# MOTORS.net
KiCad netlist of a schematic drawn in Altium Designer
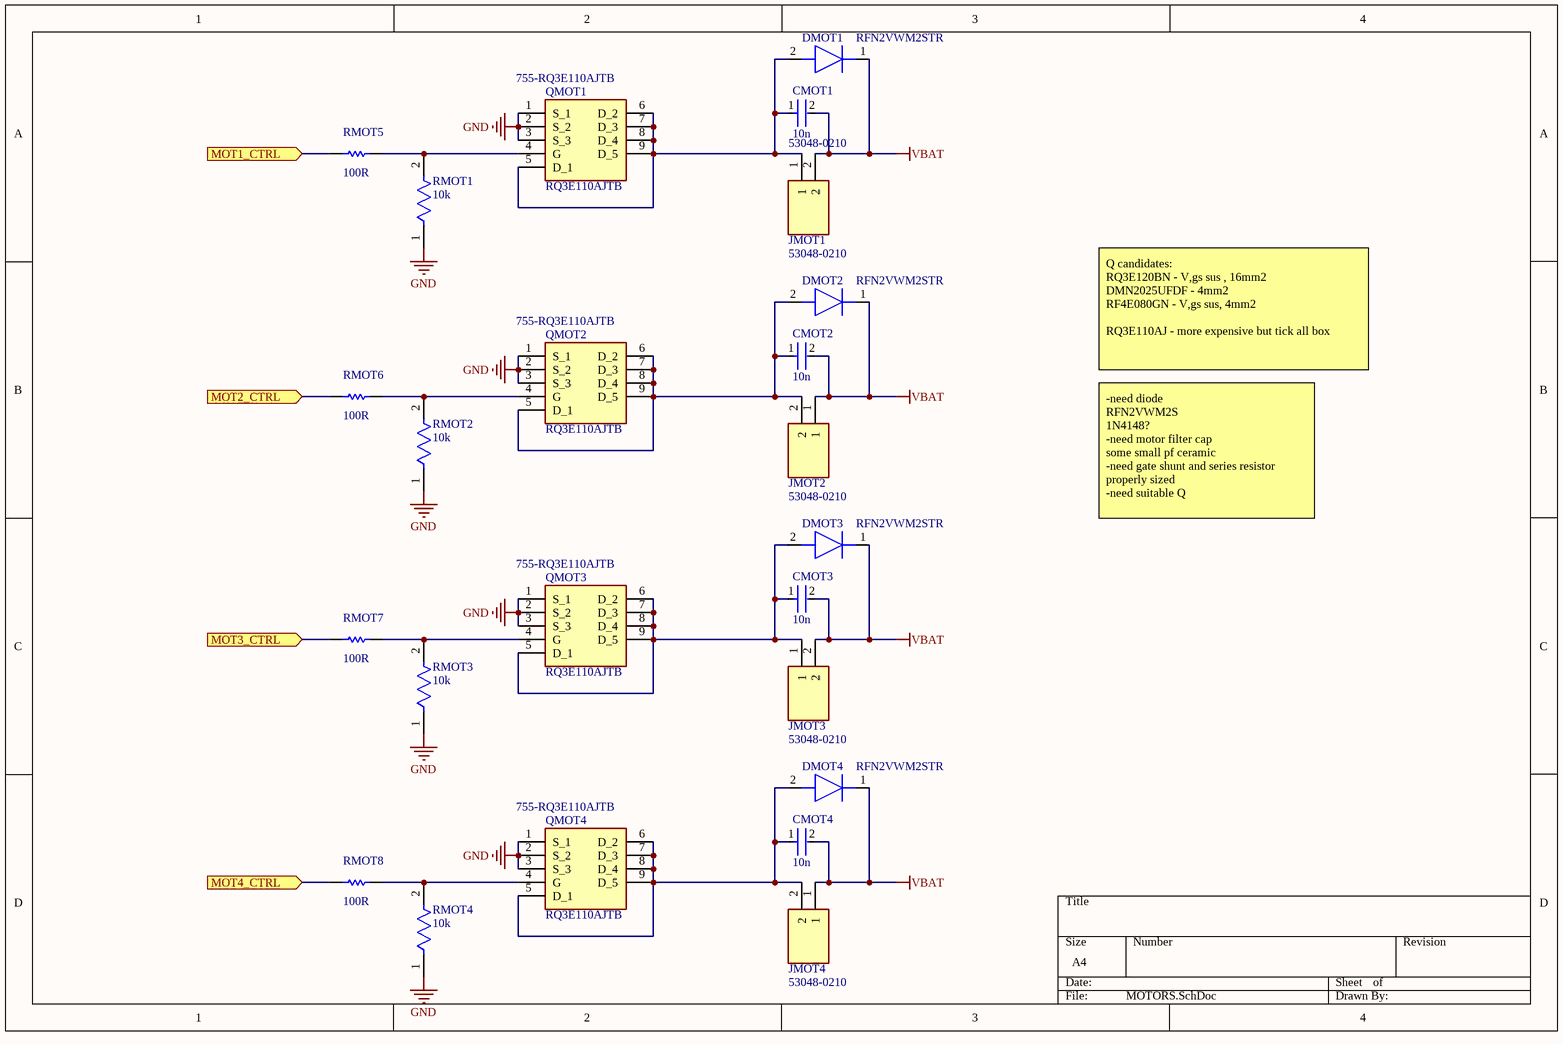
[diagram p0: MOTORS.SchDoc]

(export (version "E")
  (design (tool "Eeschema 10.0.6"))
  (components
    (comp (ref "CMOT1")
      (value "10n")
      (footprint "FP-CL10-IPC_A")
      (description "Cap Ceramic 10nF 50V X7R ±10% Pad SMD 0603 +125°C T/R")
      (fields (field (name "TOLERANCE") "10%") (field (name "VOLTAGE") "50V"))
      (libsource (lib "Altium Content Vault") (part "b4654b650e69147ec39a6b967a45e02"))
    )
    (comp (ref "CMOT2")
      (value "10n")
      (footprint "FP-CL10-IPC_A")
      (description "Cap Ceramic 10nF 50V X7R ±10% Pad SMD 0603 +125°C T/R")
      (fields (field (name "TOLERANCE") "10%") (field (name "VOLTAGE") "50V"))
      (libsource (lib "Altium Content Vault") (part "b4654b650e69147ec39a6b967a45e02"))
    )
    (comp (ref "CMOT3")
      (value "10n")
      (footprint "FP-CL10-IPC_A")
      (description "Cap Ceramic 10nF 50V X7R ±10% Pad SMD 0603 +125°C T/R")
      (fields (field (name "TOLERANCE") "10%") (field (name "VOLTAGE") "50V"))
      (libsource (lib "Altium Content Vault") (part "b4654b650e69147ec39a6b967a45e02"))
    )
    (comp (ref "CMOT4")
      (value "10n")
      (footprint "FP-CL10-IPC_A")
      (description "Cap Ceramic 10nF 50V X7R ±10% Pad SMD 0603 +125°C T/R")
      (fields (field (name "TOLERANCE") "10%") (field (name "VOLTAGE") "50V"))
      (libsource (lib "Altium Content Vault") (part "b4654b650e69147ec39a6b967a45e02"))
    )
    (comp (ref "DMOT1")
      (value "RFN2VWM2STR")
      (footprint "RFN2VWM2STR")
      (description "Diodes - General Purpose")
      (fields (field (name "MOUSER PART NUMBER") "755-RFN2VWM2STR"))
      (libsource (lib "James Whitehead") (part "RFN2VWM2STR"))
    )
    (comp (ref "DMOT2")
      (value "RFN2VWM2STR")
      (footprint "RFN2VWM2STR")
      (description "Diodes - General Purpose")
      (fields (field (name "MOUSER PART NUMBER") "755-RFN2VWM2STR"))
      (libsource (lib "James Whitehead") (part "RFN2VWM2STR"))
    )
    (comp (ref "DMOT3")
      (value "RFN2VWM2STR")
      (footprint "RFN2VWM2STR")
      (description "Diodes - General Purpose")
      (fields (field (name "MOUSER PART NUMBER") "755-RFN2VWM2STR"))
      (libsource (lib "James Whitehead") (part "RFN2VWM2STR"))
    )
    (comp (ref "DMOT4")
      (value "RFN2VWM2STR")
      (footprint "RFN2VWM2STR")
      (description "Diodes - General Purpose")
      (fields (field (name "MOUSER PART NUMBER") "755-RFN2VWM2STR"))
      (libsource (lib "James Whitehead") (part "RFN2VWM2STR"))
    )
    (comp (ref "JMOT1")
      (value "53048-0210")
      (footprint "SamacSys:SHDRRA2W35P0X125_1X2_425X550X350P")
      (description "Connector")
      (fields
        (field (name "MOUSER PART NUMBER") "538-53048-0210")
        (field (name "SUPPLIER PART NUMBER 1") "53048-0210")
      )
      (libsource (lib "*") (part "53048-0210"))
    )
    (comp (ref "JMOT2")
      (value "53048-0210")
      (footprint "SamacSys:SHDRRA2W35P0X125_1X2_425X550X350P")
      (description "Connector")
      (fields (field (name "MOUSER PART NUMBER") "538-53048-0210"))
      (libsource (lib "") (part "53048-0210_1"))
    )
    (comp (ref "JMOT3")
      (value "53048-0210")
      (footprint "SamacSys:SHDRRA2W35P0X125_1X2_425X550X350P")
      (description "Connector")
      (fields (field (name "MOUSER PART NUMBER") "538-53048-0210"))
      (libsource (lib "*") (part "53048-0210"))
    )
    (comp (ref "JMOT4")
      (value "53048-0210")
      (footprint "SamacSys:SHDRRA2W35P0X125_1X2_425X550X350P")
      (description "Connector")
      (fields (field (name "MOUSER PART NUMBER") "538-53048-0210"))
      (libsource (lib "") (part "53048-0210_1"))
    )
    (comp (ref "QMOT1")
      (value "RQ3E110AJTB")
      (footprint "SamacSys:RQ3E110AJTB")
      (description "MOSFET (N-Channel)")
      (fields
        (field (name "MOUSER PART NUMBER") "755-RQ3E110AJTB")
        (field (name "SUPPLIER PART NUMBER 1") "755-RQ3E110AJTB")
      )
      (libsource (lib "*") (part "RQ3E110AJTB"))
    )
    (comp (ref "QMOT2")
      (value "RQ3E110AJTB")
      (footprint "SamacSys:RQ3E110AJTB")
      (description "MOSFET (N-Channel)")
      (fields
        (field (name "MOUSER PART NUMBER") "755-RQ3E110AJTB")
        (field (name "SUPPLIER PART NUMBER 1") "755-RQ3E110AJTB")
      )
      (libsource (lib "*") (part "RQ3E110AJTB"))
    )
    (comp (ref "QMOT3")
      (value "RQ3E110AJTB")
      (footprint "SamacSys:RQ3E110AJTB")
      (description "MOSFET (N-Channel)")
      (fields
        (field (name "MOUSER PART NUMBER") "755-RQ3E110AJTB")
        (field (name "SUPPLIER PART NUMBER 1") "755-RQ3E110AJTB")
      )
      (libsource (lib "*") (part "RQ3E110AJTB"))
    )
    (comp (ref "QMOT4")
      (value "RQ3E110AJTB")
      (footprint "SamacSys:RQ3E110AJTB")
      (description "MOSFET (N-Channel)")
      (fields
        (field (name "MOUSER PART NUMBER") "755-RQ3E110AJTB")
        (field (name "SUPPLIER PART NUMBER 1") "755-RQ3E110AJTB")
      )
      (libsource (lib "*") (part "RQ3E110AJTB"))
    )
    (comp (ref "RMOT1")
      (value "10k")
      (footprint "FP-ERJ3G-IPC_C")
      (description "RES SMD 10K OHM 5% 1/10W 0603")
      (fields (field (name "TOLERANCE") "5%"))
      (libsource (lib "Altium Content Vault") (part "1029c3af85768c4190bb7ad29bc67b5"))
    )
    (comp (ref "RMOT2")
      (value "10k")
      (footprint "FP-ERJ3G-IPC_C")
      (description "RES SMD 10K OHM 5% 1/10W 0603")
      (fields (field (name "TOLERANCE") "5%"))
      (libsource (lib "Altium Content Vault") (part "1029c3af85768c4190bb7ad29bc67b5"))
    )
    (comp (ref "RMOT3")
      (value "10k")
      (footprint "FP-ERJ3G-IPC_C")
      (description "RES SMD 10K OHM 5% 1/10W 0603")
      (fields (field (name "TOLERANCE") "5%"))
      (libsource (lib "Altium Content Vault") (part "1029c3af85768c4190bb7ad29bc67b5"))
    )
    (comp (ref "RMOT4")
      (value "10k")
      (footprint "FP-ERJ3G-IPC_C")
      (description "RES SMD 10K OHM 5% 1/10W 0603")
      (fields (field (name "TOLERANCE") "5%"))
      (libsource (lib "Altium Content Vault") (part "1029c3af85768c4190bb7ad29bc67b5"))
    )
    (comp (ref "RMOT5")
      (value "100R")
      (footprint "RESC1608X55X30LL15T15")
      (fields (field (name "MANUFACTURER") "Panasonic") (field (name "PART NUMBER") "ERJ-3EKF1000V"))
      (libsource (lib "Altium Content Vault") (part "RES"))
    )
    (comp (ref "RMOT6")
      (value "100R")
      (footprint "RESC1608X55X30LL15T15")
      (fields (field (name "MANUFACTURER") "Panasonic") (field (name "PART NUMBER") "ERJ-3EKF1000V"))
      (libsource (lib "Altium Content Vault") (part "RES"))
    )
    (comp (ref "RMOT7")
      (value "100R")
      (footprint "RESC1608X55X30LL15T15")
      (fields (field (name "MANUFACTURER") "Panasonic") (field (name "PART NUMBER") "ERJ-3EKF1000V"))
      (libsource (lib "Altium Content Vault") (part "RES"))
    )
    (comp (ref "RMOT8")
      (value "100R")
      (footprint "RESC1608X55X30LL15T15")
      (fields (field (name "MANUFACTURER") "Panasonic") (field (name "PART NUMBER") "ERJ-3EKF1000V"))
      (libsource (lib "Altium Content Vault") (part "RES"))
    )
  )
  (nets
    (net (code "1") (name "/MOT1_CTRL") (class "Default")
      (node (ref "RMOT5") (pin "1") (pinfunction "1_1") (pintype "passive"))
    )
    (net (code "2") (name "/MOT2_CTRL") (class "Default")
      (node (ref "RMOT6") (pin "1") (pinfunction "1_1") (pintype "passive"))
    )
    (net (code "3") (name "/MOT3_CTRL") (class "Default")
      (node (ref "RMOT7") (pin "1") (pinfunction "1_1") (pintype "passive"))
    )
    (net (code "4") (name "/MOT4_CTRL") (class "Default")
      (node (ref "RMOT8") (pin "1") (pinfunction "1_1") (pintype "passive"))
    )
    (net (code "5") (name "GND") (class "Default")
      (node (ref "QMOT1") (pin "1") (pinfunction "S_1_1") (pintype "passive"))
      (node (ref "QMOT1") (pin "2") (pinfunction "S_2_2") (pintype "passive"))
      (node (ref "QMOT1") (pin "3") (pinfunction "S_3_3") (pintype "passive"))
      (node (ref "QMOT2") (pin "1") (pinfunction "S_1_1") (pintype "passive"))
      (node (ref "QMOT2") (pin "2") (pinfunction "S_2_2") (pintype "passive"))
      (node (ref "QMOT2") (pin "3") (pinfunction "S_3_3") (pintype "passive"))
      (node (ref "QMOT3") (pin "1") (pinfunction "S_1_1") (pintype "passive"))
      (node (ref "QMOT3") (pin "2") (pinfunction "S_2_2") (pintype "passive"))
      (node (ref "QMOT3") (pin "3") (pinfunction "S_3_3") (pintype "passive"))
      (node (ref "QMOT4") (pin "1") (pinfunction "S_1_1") (pintype "passive"))
      (node (ref "QMOT4") (pin "2") (pinfunction "S_2_2") (pintype "passive"))
      (node (ref "QMOT4") (pin "3") (pinfunction "S_3_3") (pintype "passive"))
      (node (ref "RMOT1") (pin "1") (pinfunction "1_1") (pintype "passive"))
      (node (ref "RMOT2") (pin "1") (pinfunction "1_1") (pintype "passive"))
      (node (ref "RMOT3") (pin "1") (pinfunction "1_1") (pintype "passive"))
      (node (ref "RMOT4") (pin "1") (pinfunction "1_1") (pintype "passive"))
    )
    (net (code "6") (name "Net-(DMOT1-A)") (class "Default")
      (node (ref "CMOT1") (pin "1") (pinfunction "1_1") (pintype "passive"))
      (node (ref "DMOT1") (pin "2") (pinfunction "A_2") (pintype "passive"))
      (node (ref "JMOT1") (pin "1") (pinfunction "1_1") (pintype "passive"))
      (node (ref "QMOT1") (pin "5") (pinfunction "D_1_5") (pintype "passive"))
      (node (ref "QMOT1") (pin "6") (pinfunction "D_2_6") (pintype "passive"))
      (node (ref "QMOT1") (pin "7") (pinfunction "D_3_7") (pintype "passive"))
      (node (ref "QMOT1") (pin "8") (pinfunction "D_4_8") (pintype "passive"))
      (node (ref "QMOT1") (pin "9") (pinfunction "D_5_9") (pintype "passive"))
    )
    (net (code "7") (name "Net-(DMOT2-A)") (class "Default")
      (node (ref "CMOT2") (pin "1") (pinfunction "1_1") (pintype "passive"))
      (node (ref "DMOT2") (pin "2") (pinfunction "A_2") (pintype "passive"))
      (node (ref "JMOT2") (pin "2") (pinfunction "2_2") (pintype "passive"))
      (node (ref "QMOT2") (pin "5") (pinfunction "D_1_5") (pintype "passive"))
      (node (ref "QMOT2") (pin "6") (pinfunction "D_2_6") (pintype "passive"))
      (node (ref "QMOT2") (pin "7") (pinfunction "D_3_7") (pintype "passive"))
      (node (ref "QMOT2") (pin "8") (pinfunction "D_4_8") (pintype "passive"))
      (node (ref "QMOT2") (pin "9") (pinfunction "D_5_9") (pintype "passive"))
    )
    (net (code "8") (name "Net-(DMOT3-A)") (class "Default")
      (node (ref "CMOT3") (pin "1") (pinfunction "1_1") (pintype "passive"))
      (node (ref "DMOT3") (pin "2") (pinfunction "A_2") (pintype "passive"))
      (node (ref "JMOT3") (pin "1") (pinfunction "1_1") (pintype "passive"))
      (node (ref "QMOT3") (pin "5") (pinfunction "D_1_5") (pintype "passive"))
      (node (ref "QMOT3") (pin "6") (pinfunction "D_2_6") (pintype "passive"))
      (node (ref "QMOT3") (pin "7") (pinfunction "D_3_7") (pintype "passive"))
      (node (ref "QMOT3") (pin "8") (pinfunction "D_4_8") (pintype "passive"))
      (node (ref "QMOT3") (pin "9") (pinfunction "D_5_9") (pintype "passive"))
    )
    (net (code "9") (name "Net-(DMOT4-A)") (class "Default")
      (node (ref "CMOT4") (pin "1") (pinfunction "1_1") (pintype "passive"))
      (node (ref "DMOT4") (pin "2") (pinfunction "A_2") (pintype "passive"))
      (node (ref "JMOT4") (pin "2") (pinfunction "2_2") (pintype "passive"))
      (node (ref "QMOT4") (pin "5") (pinfunction "D_1_5") (pintype "passive"))
      (node (ref "QMOT4") (pin "6") (pinfunction "D_2_6") (pintype "passive"))
      (node (ref "QMOT4") (pin "7") (pinfunction "D_3_7") (pintype "passive"))
      (node (ref "QMOT4") (pin "8") (pinfunction "D_4_8") (pintype "passive"))
      (node (ref "QMOT4") (pin "9") (pinfunction "D_5_9") (pintype "passive"))
    )
    (net (code "10") (name "Net-(QMOT1-G)") (class "Default")
      (node (ref "QMOT1") (pin "4") (pinfunction "G_4") (pintype "passive"))
      (node (ref "RMOT1") (pin "2") (pinfunction "2_2") (pintype "passive"))
      (node (ref "RMOT5") (pin "2") (pinfunction "2_2") (pintype "passive"))
    )
    (net (code "11") (name "Net-(QMOT2-G)") (class "Default")
      (node (ref "QMOT2") (pin "4") (pinfunction "G_4") (pintype "passive"))
      (node (ref "RMOT2") (pin "2") (pinfunction "2_2") (pintype "passive"))
      (node (ref "RMOT6") (pin "2") (pinfunction "2_2") (pintype "passive"))
    )
    (net (code "12") (name "Net-(QMOT3-G)") (class "Default")
      (node (ref "QMOT3") (pin "4") (pinfunction "G_4") (pintype "passive"))
      (node (ref "RMOT3") (pin "2") (pinfunction "2_2") (pintype "passive"))
      (node (ref "RMOT7") (pin "2") (pinfunction "2_2") (pintype "passive"))
    )
    (net (code "13") (name "Net-(QMOT4-G)") (class "Default")
      (node (ref "QMOT4") (pin "4") (pinfunction "G_4") (pintype "passive"))
      (node (ref "RMOT4") (pin "2") (pinfunction "2_2") (pintype "passive"))
      (node (ref "RMOT8") (pin "2") (pinfunction "2_2") (pintype "passive"))
    )
    (net (code "14") (name "VBAT") (class "Default")
      (node (ref "CMOT1") (pin "2") (pinfunction "2_2") (pintype "passive"))
      (node (ref "CMOT2") (pin "2") (pinfunction "2_2") (pintype "passive"))
      (node (ref "CMOT3") (pin "2") (pinfunction "2_2") (pintype "passive"))
      (node (ref "CMOT4") (pin "2") (pinfunction "2_2") (pintype "passive"))
      (node (ref "DMOT1") (pin "1") (pinfunction "K_1") (pintype "passive"))
      (node (ref "DMOT2") (pin "1") (pinfunction "K_1") (pintype "passive"))
      (node (ref "DMOT3") (pin "1") (pinfunction "K_1") (pintype "passive"))
      (node (ref "DMOT4") (pin "1") (pinfunction "K_1") (pintype "passive"))
      (node (ref "JMOT1") (pin "2") (pinfunction "2_2") (pintype "passive"))
      (node (ref "JMOT2") (pin "1") (pinfunction "1_1") (pintype "passive"))
      (node (ref "JMOT3") (pin "2") (pinfunction "2_2") (pintype "passive"))
      (node (ref "JMOT4") (pin "1") (pinfunction "1_1") (pintype "passive"))
    )
  )
)
